# Pi_USB_2_UART.net
KiCad netlist of a schematic drawn in Altium Designer
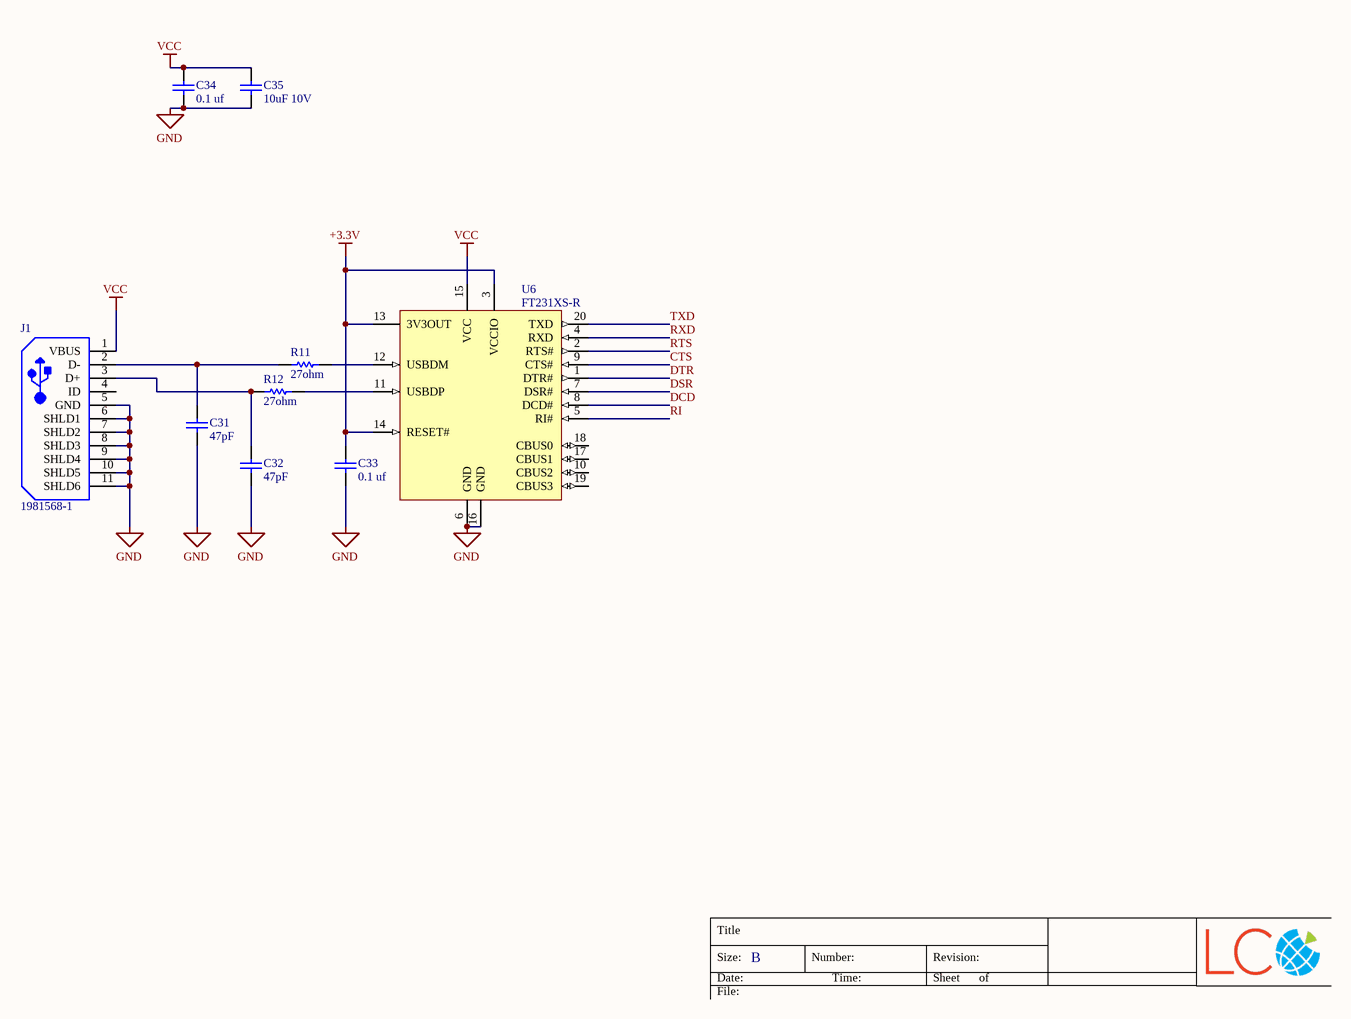
[diagram p0: Pi_USB_2_UART.SchDoc]

(export (version "E")
  (design (tool "Eeschema 10.0.6"))
  (components
    (comp (ref "C31")
      (value "47pF")
      (footprint "CAPC1005X61X26NL10T16")
      (description "VJ0402D470JXAAJ")
      (fields (field (name "MANUFACTURER") "Vitramon"))
      (libsource (lib "Altium Content Vault") (part "CAP"))
    )
    (comp (ref "C32")
      (value "47pF")
      (footprint "CAPC1005X61X26NL10T16")
      (description "VJ0402D470JXAAJ")
      (fields (field (name "MANUFACTURER") "Vitramon"))
      (libsource (lib "Altium Content Vault") (part "CAP"))
    )
    (comp (ref "C33")
      (value "0.1 uf")
      (footprint "CAPC1608X92X38LL15T08")
      (description "VJ0603Y104KNXAO")
      (fields (field (name "MANUFACTURER") "Vitramon"))
      (libsource (lib "Altium Content Vault") (part "CAP"))
    )
    (comp (ref "C34")
      (value "0.1 uf")
      (footprint "CAPC1608X92X38LL15T08")
      (description "VJ0603Y104KNXAO")
      (fields (field (name "MANUFACTURER") "Vitramon"))
      (libsource (lib "Altium Content Vault") (part "CAP"))
    )
    (comp (ref "C35")
      (value "10uF 10V")
      (footprint "CAPC1609X100X15LL20")
      (description "TACL106M010XTA")
      (fields (field (name "MANUFACTURER") "AVX Interconnect / Elco"))
      (libsource (lib "Altium Content Vault") (part "CAP"))
    )
    (comp (ref "J1")
      (value "1981568-1")
      (footprint "TECO-1981568-5_V")
      (description "Micro USB Receptacle Standard Type B Assy, 5-Pin SMD, RoHS, Tape and Reel")
      (fields (field (name "MANUFACTURER") "TE Connectivity"))
      (libsource (lib "Altium Content Vault") (part "USB-5-6SHLD"))
    )
    (comp (ref "R11")
      (value "27ohm")
      (footprint "RESC1005X40X25ML05T05")
      (description "CRCW0402270RFKED")
      (fields (field (name "MANUFACTURER") "Vishay Dale"))
      (libsource (lib "Altium Content Vault") (part "RES"))
    )
    (comp (ref "R12")
      (value "27ohm")
      (footprint "RESC1005X40X25ML05T05")
      (description "CRCW0402270RFKED")
      (fields (field (name "MANUFACTURER") "Vishay Dale"))
      (libsource (lib "Altium Content Vault") (part "RES"))
    )
    (comp (ref "U6")
      (value "FT231XS-R")
      (footprint "SSOP-20_L")
      (fields (field (name "MANUFACTURER") "FTDI"))
      (libsource (lib "Altium Content Vault") (part "COM-USB-FT231XS-IL20"))
    )
  )
  (nets
    (net (code "1") (name "+3.3V") (class "Default")
      (node (ref "C33") (pin "2") (pinfunction "2_2") (pintype "passive"))
      (node (ref "U6") (pin "13") (pinfunction "3V3OUT_13") (pintype "power_in"))
      (node (ref "U6") (pin "14") (pinfunction "RESET#_14") (pintype "input"))
      (node (ref "U6") (pin "3") (pinfunction "VCCIO_3") (pintype "power_in"))
    )
    (net (code "2") (name "/CTS") (class "Default")
      (node (ref "U6") (pin "9") (pinfunction "CTS#_9") (pintype "input"))
    )
    (net (code "3") (name "/DCD") (class "Default")
      (node (ref "U6") (pin "8") (pinfunction "DCD#_8") (pintype "input"))
    )
    (net (code "4") (name "/DSR") (class "Default")
      (node (ref "U6") (pin "7") (pinfunction "DSR#_7") (pintype "input"))
    )
    (net (code "5") (name "/DTR") (class "Default")
      (node (ref "U6") (pin "1") (pinfunction "DTR#_1") (pintype "output"))
    )
    (net (code "6") (name "/RI") (class "Default")
      (node (ref "U6") (pin "5") (pinfunction "RI#_5") (pintype "input"))
    )
    (net (code "7") (name "/RTS") (class "Default")
      (node (ref "U6") (pin "2") (pinfunction "RTS#_2") (pintype "output"))
    )
    (net (code "8") (name "/RXD") (class "Default")
      (node (ref "U6") (pin "4") (pinfunction "RXD_4") (pintype "input"))
    )
    (net (code "9") (name "/TXD") (class "Default")
      (node (ref "U6") (pin "20") (pinfunction "TXD_20") (pintype "output"))
    )
    (net (code "10") (name "GND") (class "Default")
      (node (ref "C31") (pin "1") (pinfunction "1_1") (pintype "passive"))
      (node (ref "C32") (pin "1") (pinfunction "1_1") (pintype "passive"))
      (node (ref "C33") (pin "1") (pinfunction "1_1") (pintype "passive"))
      (node (ref "C34") (pin "1") (pinfunction "1_1") (pintype "passive"))
      (node (ref "C35") (pin "1") (pinfunction "1_1") (pintype "passive"))
      (node (ref "J1") (pin "10") (pinfunction "SHLD5_10") (pintype "passive"))
      (node (ref "J1") (pin "11") (pinfunction "SHLD6_11") (pintype "passive"))
      (node (ref "J1") (pin "5") (pinfunction "GND_5") (pintype "passive"))
      (node (ref "J1") (pin "6") (pinfunction "SHLD1_6") (pintype "passive"))
      (node (ref "J1") (pin "7") (pinfunction "SHLD2_7") (pintype "passive"))
      (node (ref "J1") (pin "8") (pinfunction "SHLD3_8") (pintype "passive"))
      (node (ref "J1") (pin "9") (pinfunction "SHLD4_9") (pintype "passive"))
      (node (ref "U6") (pin "16") (pinfunction "GND_16") (pintype "power_in"))
      (node (ref "U6") (pin "6") (pinfunction "GND_6") (pintype "power_in"))
    )
    (net (code "11") (name "Net-(J1-D+)") (class "Default")
      (node (ref "C32") (pin "2") (pinfunction "2_2") (pintype "passive"))
      (node (ref "J1") (pin "3") (pinfunction "D+_3") (pintype "passive"))
      (node (ref "R12") (pin "1") (pinfunction "1_1") (pintype "passive"))
    )
    (net (code "12") (name "Net-(J1-D-)") (class "Default")
      (node (ref "C31") (pin "2") (pinfunction "2_2") (pintype "passive"))
      (node (ref "J1") (pin "2") (pinfunction "D-_2") (pintype "passive"))
      (node (ref "R11") (pin "1") (pinfunction "1_1") (pintype "passive"))
    )
    (net (code "13") (name "Net-(U6-USBDM)") (class "Default")
      (node (ref "R11") (pin "2") (pinfunction "2_2") (pintype "passive"))
      (node (ref "U6") (pin "12") (pinfunction "USBDM_12") (pintype "input"))
    )
    (net (code "14") (name "Net-(U6-USBDP)") (class "Default")
      (node (ref "R12") (pin "2") (pinfunction "2_2") (pintype "passive"))
      (node (ref "U6") (pin "11") (pinfunction "USBDP_11") (pintype "input"))
    )
    (net (code "15") (name "VCC") (class "Default")
      (node (ref "C34") (pin "2") (pinfunction "2_2") (pintype "passive"))
      (node (ref "C35") (pin "2") (pinfunction "2_2") (pintype "passive"))
      (node (ref "J1") (pin "1") (pinfunction "VBUS_1") (pintype "passive"))
      (node (ref "U6") (pin "15") (pinfunction "VCC_15") (pintype "power_in"))
    )
    (net (code "16") (name "unconnected-(J1-ID-Pad4)") (class "Default")
      (node (ref "J1") (pin "4") (pinfunction "ID_4") (pintype "passive"))
    )
    (net (code "17") (name "unconnected-(U6-CBUS0-Pad18)") (class "Default")
      (node (ref "U6") (pin "18") (pinfunction "CBUS0_18") (pintype "bidirectional"))
    )
    (net (code "18") (name "unconnected-(U6-CBUS1-Pad17)") (class "Default")
      (node (ref "U6") (pin "17") (pinfunction "CBUS1_17") (pintype "bidirectional"))
    )
    (net (code "19") (name "unconnected-(U6-CBUS2-Pad10)") (class "Default")
      (node (ref "U6") (pin "10") (pinfunction "CBUS2_10") (pintype "bidirectional"))
    )
    (net (code "20") (name "unconnected-(U6-CBUS3-Pad19)") (class "Default")
      (node (ref "U6") (pin "19") (pinfunction "CBUS3_19") (pintype "bidirectional"))
    )
  )
)
